# open-usb-can-rev2.net
KiCad netlist of a schematic drawn in EAGLE
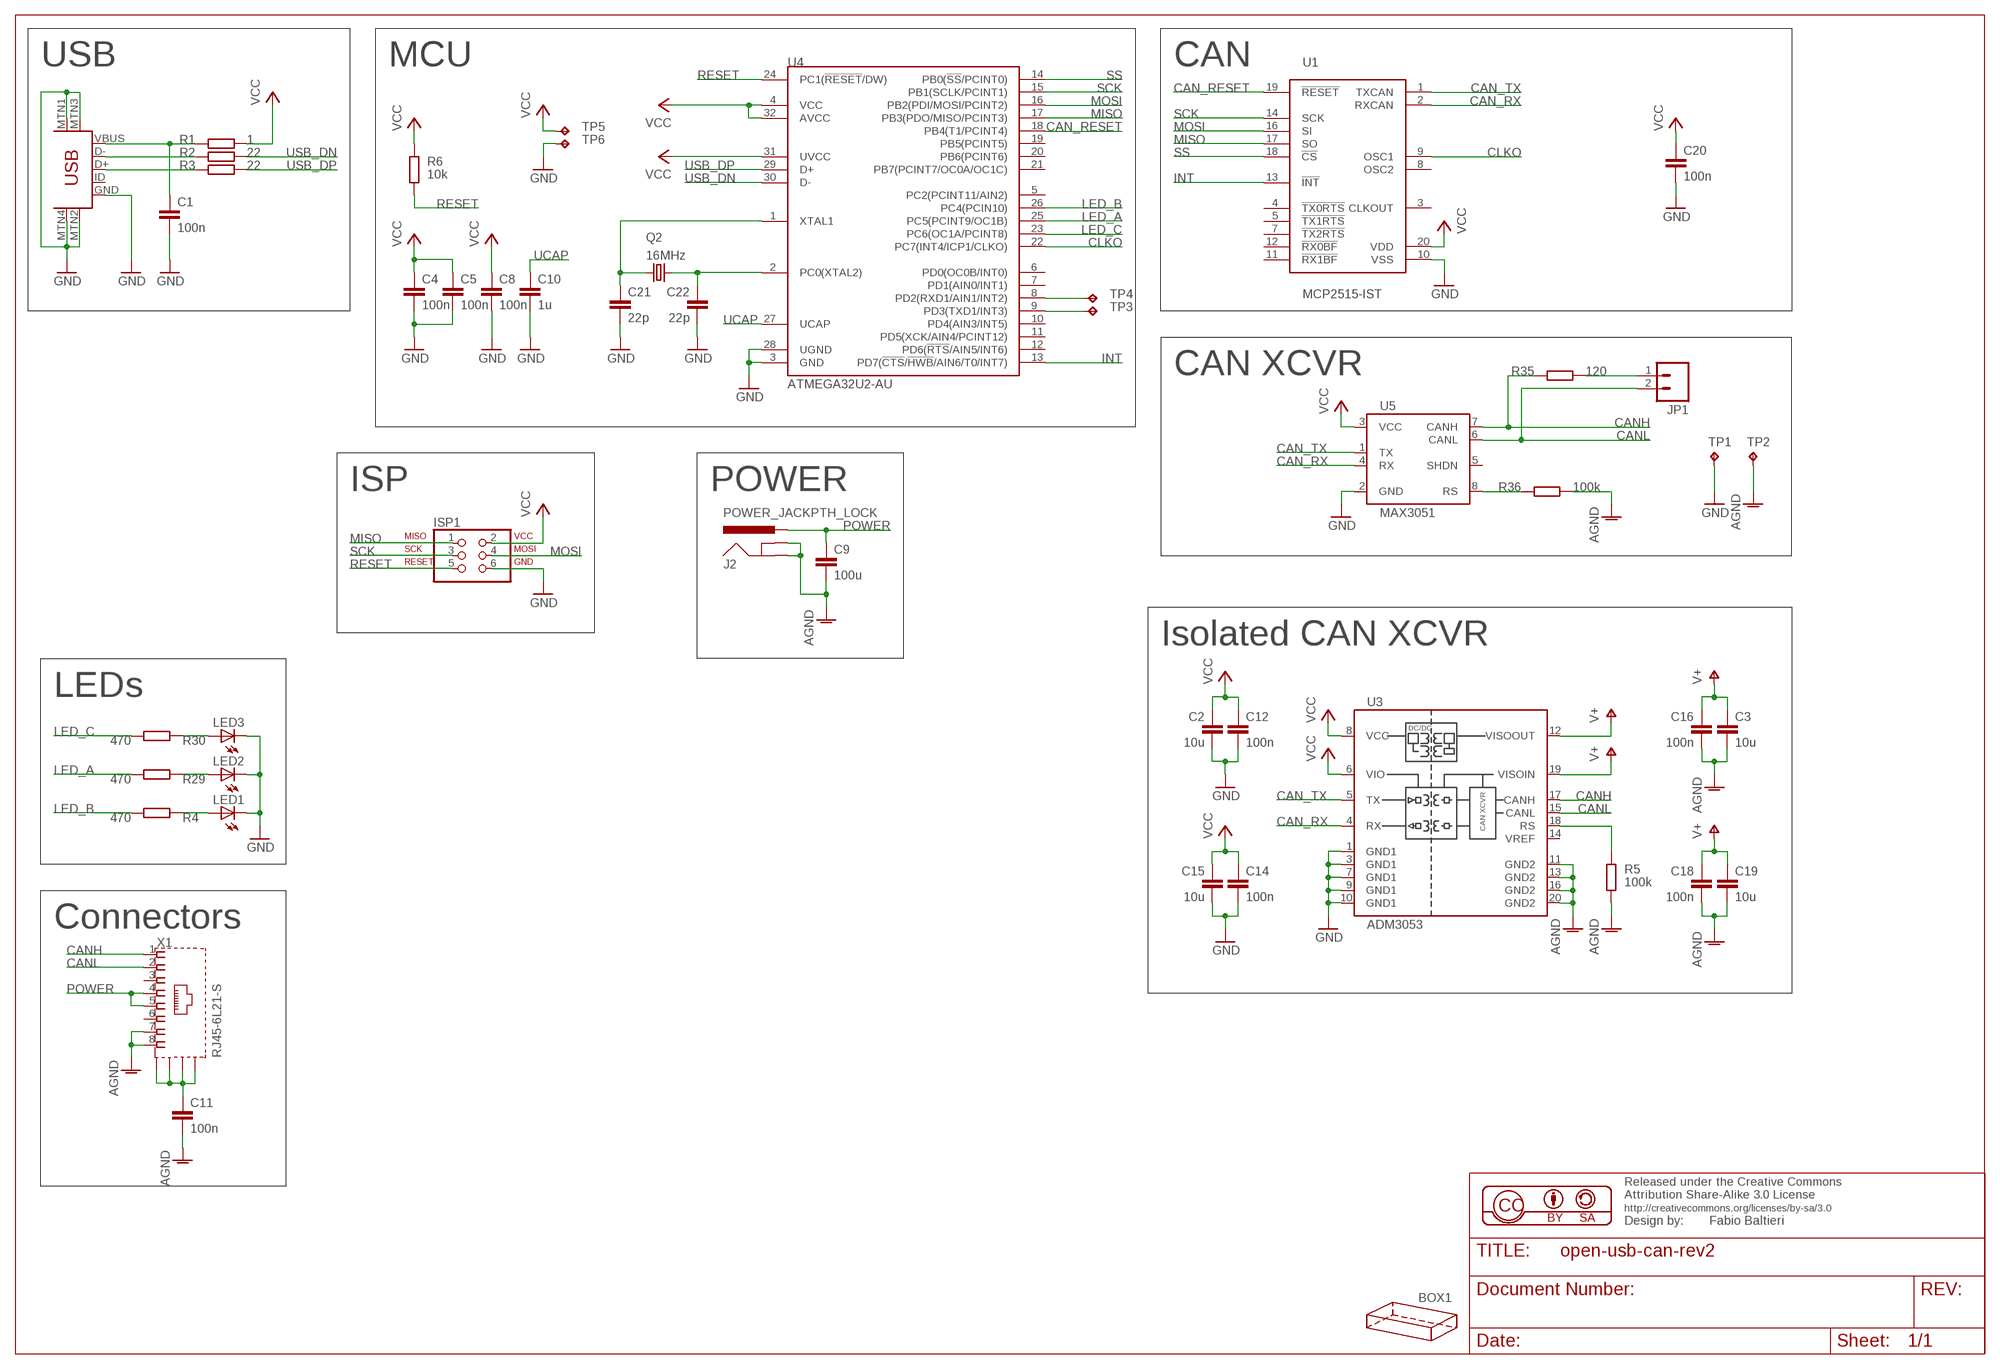
[diagram p0: schematic, sheet 1]

(export (version "E")
  (design (tool "Eeschema 10.0.6"))
  (components
    (comp (ref "BOX1")
      (value "HAMMOND-BOX-R")
      (footprint "eagle-import:1151R")
      (libsource (lib "eagle-import") (part "HAMMOND-BOX-R"))
    )
    (comp (ref "C1")
      (value "100n")
      (footprint "eagle-import:C0805")
      (libsource (lib "eagle-import") (part "C-EUC0805"))
    )
    (comp (ref "C2")
      (value "10u")
      (footprint "eagle-import:C0805")
      (libsource (lib "eagle-import") (part "C-EUC0805"))
    )
    (comp (ref "C3")
      (value "10u")
      (footprint "eagle-import:C0805")
      (libsource (lib "eagle-import") (part "C-EUC0805"))
    )
    (comp (ref "C4")
      (value "100n")
      (footprint "eagle-import:C0805")
      (libsource (lib "eagle-import") (part "C-EUC0805"))
    )
    (comp (ref "C5")
      (value "100n")
      (footprint "eagle-import:C0805")
      (libsource (lib "eagle-import") (part "C-EUC0805"))
    )
    (comp (ref "C8")
      (value "100n")
      (footprint "eagle-import:C0805")
      (libsource (lib "eagle-import") (part "C-EUC0805"))
    )
    (comp (ref "C9")
      (value "100u")
      (footprint "eagle-import:C0805")
      (libsource (lib "eagle-import") (part "C-EUC0805"))
    )
    (comp (ref "C10")
      (value "1u")
      (footprint "eagle-import:C0805")
      (libsource (lib "eagle-import") (part "C-EUC0805"))
    )
    (comp (ref "C11")
      (value "100n")
      (footprint "eagle-import:C0805")
      (libsource (lib "eagle-import") (part "C-EUC0805"))
    )
    (comp (ref "C12")
      (value "100n")
      (footprint "eagle-import:C0805")
      (libsource (lib "eagle-import") (part "C-EUC0805"))
    )
    (comp (ref "C14")
      (value "100n")
      (footprint "eagle-import:C0805")
      (libsource (lib "eagle-import") (part "C-EUC0805"))
    )
    (comp (ref "C15")
      (value "10u")
      (footprint "eagle-import:C0805")
      (libsource (lib "eagle-import") (part "C-EUC0805"))
    )
    (comp (ref "C16")
      (value "100n")
      (footprint "eagle-import:C0805")
      (libsource (lib "eagle-import") (part "C-EUC0805"))
    )
    (comp (ref "C18")
      (value "100n")
      (footprint "eagle-import:C0805")
      (libsource (lib "eagle-import") (part "C-EUC0805"))
    )
    (comp (ref "C19")
      (value "10u")
      (footprint "eagle-import:C0805")
      (libsource (lib "eagle-import") (part "C-EUC0805"))
    )
    (comp (ref "C20")
      (value "100n")
      (footprint "eagle-import:C0805")
      (libsource (lib "eagle-import") (part "C-EUC0805"))
    )
    (comp (ref "C21")
      (value "22p")
      (footprint "eagle-import:C0805")
      (libsource (lib "eagle-import") (part "C-EUC0805"))
    )
    (comp (ref "C22")
      (value "22p")
      (footprint "eagle-import:C0805")
      (libsource (lib "eagle-import") (part "C-EUC0805"))
    )
    (comp (ref "ISP1")
      (value "ISP-AVR910PTH")
      (footprint "eagle-import:2X03")
      (libsource (lib "eagle-import") (part "ISP-AVR910PTH"))
    )
    (comp (ref "J2")
      (value "POWER_JACKPTH_LOCK")
      (footprint "eagle-import:POWER_JACK_PTH_LOCK")
      (libsource (lib "eagle-import") (part "POWER_JACKPTH_LOCK"))
    )
    (comp (ref "JP1")
      (value "M02PTH")
      (footprint "eagle-import:1X02")
      (libsource (lib "eagle-import") (part "M02PTH"))
    )
    (comp (ref "LED1")
      (value "LEDCHIPLED_0805")
      (footprint "eagle-import:CHIPLED_0805")
      (libsource (lib "eagle-import") (part "LEDCHIPLED_0805"))
    )
    (comp (ref "LED2")
      (value "LEDCHIPLED_0805")
      (footprint "eagle-import:CHIPLED_0805")
      (libsource (lib "eagle-import") (part "LEDCHIPLED_0805"))
    )
    (comp (ref "LED3")
      (value "LEDCHIPLED_0805")
      (footprint "eagle-import:CHIPLED_0805")
      (libsource (lib "eagle-import") (part "LEDCHIPLED_0805"))
    )
    (comp (ref "Q2")
      (value "16MHz")
      (footprint "eagle-import:CRYSTAL-SMD-5X3")
      (libsource (lib "eagle-import") (part "CRYSTAL5X3"))
    )
    (comp (ref "R1")
      (value "1")
      (footprint "eagle-import:R0603")
      (libsource (lib "eagle-import") (part "R-EU_R0603"))
    )
    (comp (ref "R2")
      (value "22")
      (footprint "eagle-import:R0603")
      (libsource (lib "eagle-import") (part "R-EU_R0603"))
    )
    (comp (ref "R3")
      (value "22")
      (footprint "eagle-import:R0603")
      (libsource (lib "eagle-import") (part "R-EU_R0603"))
    )
    (comp (ref "R4")
      (value "470")
      (footprint "eagle-import:R0603")
      (libsource (lib "eagle-import") (part "R-EU_R0603"))
    )
    (comp (ref "R5")
      (value "100k")
      (footprint "eagle-import:R0603")
      (libsource (lib "eagle-import") (part "R-EU_R0603"))
    )
    (comp (ref "R6")
      (value "10k")
      (footprint "eagle-import:R0603")
      (libsource (lib "eagle-import") (part "R-EU_R0603"))
    )
    (comp (ref "R29")
      (value "470")
      (footprint "eagle-import:R0603")
      (libsource (lib "eagle-import") (part "R-EU_R0603"))
    )
    (comp (ref "R30")
      (value "470")
      (footprint "eagle-import:R0603")
      (libsource (lib "eagle-import") (part "R-EU_R0603"))
    )
    (comp (ref "R35")
      (value "120")
      (footprint "eagle-import:R0805")
      (libsource (lib "eagle-import") (part "R-EU_R0805"))
    )
    (comp (ref "R36")
      (value "100k")
      (footprint "eagle-import:R0603")
      (libsource (lib "eagle-import") (part "R-EU_R0603"))
    )
    (comp (ref "TP1")
      (value "TPTP16SQ")
      (footprint "eagle-import:TP16SQ")
      (libsource (lib "eagle-import") (part "TPTP16SQ"))
    )
    (comp (ref "TP2")
      (value "TPTP16SQ")
      (footprint "eagle-import:TP16SQ")
      (libsource (lib "eagle-import") (part "TPTP16SQ"))
    )
    (comp (ref "TP3")
      (value "TPTP11R")
      (footprint "eagle-import:TP11R")
      (libsource (lib "eagle-import") (part "TPTP11R"))
    )
    (comp (ref "TP4")
      (value "TPTP11R")
      (footprint "eagle-import:TP11R")
      (libsource (lib "eagle-import") (part "TPTP11R"))
    )
    (comp (ref "TP5")
      (value "TPTP11R")
      (footprint "eagle-import:TP11R")
      (libsource (lib "eagle-import") (part "TPTP11R"))
    )
    (comp (ref "TP6")
      (value "TPTP11R")
      (footprint "eagle-import:TP11R")
      (libsource (lib "eagle-import") (part "TPTP11R"))
    )
    (comp (ref "U$2")
      (value "USB-MINIB-5PIN")
      (footprint "eagle-import:USB-MINIB")
      (libsource (lib "eagle-import") (part "USB-MINIB-5PIN"))
    )
    (comp (ref "U1")
      (value "MCP2515-IST")
      (footprint "eagle-import:TSSOP20")
      (libsource (lib "eagle-import") (part "MCP2515-IST"))
    )
    (comp (ref "U3")
      (value "ADM3053")
      (footprint "eagle-import:SO20W")
      (libsource (lib "eagle-import") (part "ADM3053"))
    )
    (comp (ref "U4")
      (value "ATMEGA32U2-AU")
      (footprint "eagle-import:TQFP32-08")
      (libsource (lib "eagle-import") (part "ATMEGA32U2-AU"))
    )
    (comp (ref "U5")
      (value "MAX3051")
      (footprint "eagle-import:SO08")
      (libsource (lib "eagle-import") (part "MAX3051"))
    )
    (comp (ref "X1")
      (value "RJ45-6L21-S")
      (footprint "eagle-import:RJ45-SHIELD1")
      (libsource (lib "eagle-import") (part "RJ4521-S-6L"))
    )
  )
  (nets
    (net (code "1") (name "/CANH") (class "Default")
      (node (ref "R35") (pin "1") (pinfunction "1_1") (pintype "passive"))
      (node (ref "U3") (pin "17") (pinfunction "CANH_17") (pintype "bidirectional"))
      (node (ref "U5") (pin "7") (pinfunction "CANH_7") (pintype "bidirectional"))
      (node (ref "X1") (pin "1") (pinfunction "1_1") (pintype "passive"))
    )
    (net (code "2") (name "/CANL") (class "Default")
      (node (ref "JP1") (pin "2") (pinfunction "2_2") (pintype "passive"))
      (node (ref "U3") (pin "15") (pinfunction "CANL_15") (pintype "bidirectional"))
      (node (ref "U5") (pin "6") (pinfunction "CANL_6") (pintype "bidirectional"))
      (node (ref "X1") (pin "2") (pinfunction "2_2") (pintype "passive"))
    )
    (net (code "3") (name "/CAN_RESET") (class "Default")
      (node (ref "U1") (pin "19") (pinfunction "~{RESET}_19") (pintype "bidirectional"))
      (node (ref "U4") (pin "18") (pinfunction "PB4(T1/PCINT4)_18") (pintype "bidirectional"))
    )
    (net (code "4") (name "/CAN_RX") (class "Default")
      (node (ref "U1") (pin "2") (pinfunction "RXCAN_2") (pintype "bidirectional"))
      (node (ref "U3") (pin "4") (pinfunction "RX_4") (pintype "bidirectional"))
      (node (ref "U5") (pin "4") (pinfunction "RX_4") (pintype "bidirectional"))
    )
    (net (code "5") (name "/CAN_TX") (class "Default")
      (node (ref "U1") (pin "1") (pinfunction "TXCAN_1") (pintype "bidirectional"))
      (node (ref "U3") (pin "5") (pinfunction "TX_5") (pintype "bidirectional"))
      (node (ref "U5") (pin "1") (pinfunction "TX_1") (pintype "bidirectional"))
    )
    (net (code "6") (name "/CLKO") (class "Default")
      (node (ref "U1") (pin "9") (pinfunction "OSC1_9") (pintype "bidirectional"))
      (node (ref "U4") (pin "22") (pinfunction "PC7(INT4/ICP1/CLKO)_22") (pintype "bidirectional"))
    )
    (net (code "7") (name "/INT") (class "Default")
      (node (ref "U1") (pin "13") (pinfunction "~{INT}_13") (pintype "bidirectional"))
      (node (ref "U4") (pin "13") (pinfunction "PD7(~{CTS}/~{HWB}/AIN6/T0/INT7)_13") (pintype "bidirectional"))
    )
    (net (code "8") (name "/LED_A") (class "Default")
      (node (ref "R29") (pin "2") (pinfunction "2_2") (pintype "passive"))
      (node (ref "U4") (pin "25") (pinfunction "PC5(PCINT9/OC1B)_25") (pintype "bidirectional"))
    )
    (net (code "9") (name "/LED_B") (class "Default")
      (node (ref "R4") (pin "2") (pinfunction "2_2") (pintype "passive"))
      (node (ref "U4") (pin "26") (pinfunction "PC4(PCIN10)_26") (pintype "bidirectional"))
    )
    (net (code "10") (name "/LED_C") (class "Default")
      (node (ref "R30") (pin "2") (pinfunction "2_2") (pintype "passive"))
      (node (ref "U4") (pin "23") (pinfunction "PC6(OC1A/PCINT8)_23") (pintype "bidirectional"))
    )
    (net (code "11") (name "/MISO") (class "Default")
      (node (ref "ISP1") (pin "1") (pinfunction "1_1") (pintype "passive"))
      (node (ref "U1") (pin "17") (pinfunction "SO_17") (pintype "bidirectional"))
      (node (ref "U4") (pin "17") (pinfunction "PB3(PDO/MISO/PCINT3)_17") (pintype "bidirectional"))
    )
    (net (code "12") (name "/MOSI") (class "Default")
      (node (ref "ISP1") (pin "4") (pinfunction "4_4") (pintype "passive"))
      (node (ref "U1") (pin "16") (pinfunction "SI_16") (pintype "bidirectional"))
      (node (ref "U4") (pin "16") (pinfunction "PB2(PDI/MOSI/PCINT2)_16") (pintype "bidirectional"))
    )
    (net (code "13") (name "/POWER") (class "Default")
      (node (ref "C9") (pin "1") (pinfunction "1_1") (pintype "passive"))
      (node (ref "J2") (pin "PWR") (pinfunction "PWR_PWR") (pintype "bidirectional"))
      (node (ref "X1") (pin "4") (pinfunction "4_4") (pintype "passive"))
      (node (ref "X1") (pin "5") (pinfunction "5_5") (pintype "passive"))
    )
    (net (code "14") (name "/RESET") (class "Default")
      (node (ref "ISP1") (pin "5") (pinfunction "5_5") (pintype "passive"))
      (node (ref "R6") (pin "2") (pinfunction "2_2") (pintype "passive"))
      (node (ref "U4") (pin "24") (pinfunction "PC1(~{RESET}/DW)_24") (pintype "bidirectional"))
    )
    (net (code "15") (name "/SCK") (class "Default")
      (node (ref "ISP1") (pin "3") (pinfunction "3_3") (pintype "passive"))
      (node (ref "U1") (pin "14") (pinfunction "SCK_14") (pintype "bidirectional"))
      (node (ref "U4") (pin "15") (pinfunction "PB1(SCLK/PCINT1)_15") (pintype "bidirectional"))
    )
    (net (code "16") (name "/SS") (class "Default")
      (node (ref "U1") (pin "18") (pinfunction "~{CS}_18") (pintype "bidirectional"))
      (node (ref "U4") (pin "14") (pinfunction "PB0(~{SS}/PCINT0)_14") (pintype "bidirectional"))
    )
    (net (code "17") (name "/UCAP") (class "Default")
      (node (ref "C10") (pin "1") (pinfunction "1_1") (pintype "passive"))
      (node (ref "U4") (pin "27") (pinfunction "UCAP_27") (pintype "bidirectional"))
    )
    (net (code "18") (name "/USB_DN") (class "Default")
      (node (ref "R2") (pin "2") (pinfunction "2_2") (pintype "passive"))
      (node (ref "U4") (pin "30") (pinfunction "D-_30") (pintype "bidirectional"))
    )
    (net (code "19") (name "/USB_DP") (class "Default")
      (node (ref "R3") (pin "2") (pinfunction "2_2") (pintype "passive"))
      (node (ref "U4") (pin "29") (pinfunction "D+_29") (pintype "bidirectional"))
    )
    (net (code "20") (name "AGND") (class "Default")
      (node (ref "C11") (pin "2") (pinfunction "2_2") (pintype "passive"))
      (node (ref "C16") (pin "2") (pinfunction "2_2") (pintype "passive"))
      (node (ref "C18") (pin "2") (pinfunction "2_2") (pintype "passive"))
      (node (ref "C19") (pin "2") (pinfunction "2_2") (pintype "passive"))
      (node (ref "C3") (pin "2") (pinfunction "2_2") (pintype "passive"))
      (node (ref "C9") (pin "2") (pinfunction "2_2") (pintype "passive"))
      (node (ref "J2") (pin "GND") (pinfunction "GND_GND") (pintype "bidirectional"))
      (node (ref "J2") (pin "GNDBREAK") (pinfunction "GNDBREAK_GNDBREAK") (pintype "bidirectional"))
      (node (ref "R36") (pin "2") (pinfunction "2_2") (pintype "passive"))
      (node (ref "R5") (pin "2") (pinfunction "2_2") (pintype "passive"))
      (node (ref "TP2") (pin "TP") (pinfunction "TP_TP") (pintype "input"))
      (node (ref "U3") (pin "11") (pinfunction "GND2_11") (pintype "bidirectional"))
      (node (ref "U3") (pin "13") (pinfunction "GND2_13") (pintype "bidirectional"))
      (node (ref "U3") (pin "16") (pinfunction "GND2_16") (pintype "bidirectional"))
      (node (ref "U3") (pin "20") (pinfunction "GND2_20") (pintype "bidirectional"))
      (node (ref "X1") (pin "7") (pinfunction "7_7") (pintype "passive"))
      (node (ref "X1") (pin "8") (pinfunction "8_8") (pintype "passive"))
    )
    (net (code "21") (name "GND") (class "Default")
      (node (ref "C1") (pin "2") (pinfunction "2_2") (pintype "passive"))
      (node (ref "C10") (pin "2") (pinfunction "2_2") (pintype "passive"))
      (node (ref "C12") (pin "2") (pinfunction "2_2") (pintype "passive"))
      (node (ref "C14") (pin "2") (pinfunction "2_2") (pintype "passive"))
      (node (ref "C15") (pin "2") (pinfunction "2_2") (pintype "passive"))
      (node (ref "C2") (pin "2") (pinfunction "2_2") (pintype "passive"))
      (node (ref "C20") (pin "2") (pinfunction "2_2") (pintype "passive"))
      (node (ref "C21") (pin "2") (pinfunction "2_2") (pintype "passive"))
      (node (ref "C22") (pin "2") (pinfunction "2_2") (pintype "passive"))
      (node (ref "C4") (pin "2") (pinfunction "2_2") (pintype "passive"))
      (node (ref "C5") (pin "2") (pinfunction "2_2") (pintype "passive"))
      (node (ref "C8") (pin "2") (pinfunction "2_2") (pintype "passive"))
      (node (ref "ISP1") (pin "6") (pinfunction "6_6") (pintype "passive"))
      (node (ref "LED1") (pin "C") (pinfunction "C_C") (pintype "passive"))
      (node (ref "LED2") (pin "C") (pinfunction "C_C") (pintype "passive"))
      (node (ref "LED3") (pin "C") (pinfunction "C_C") (pintype "passive"))
      (node (ref "TP1") (pin "TP") (pinfunction "TP_TP") (pintype "input"))
      (node (ref "TP6") (pin "TP") (pinfunction "TP_TP") (pintype "input"))
      (node (ref "U$2") (pin "GND") (pinfunction "GND_GND") (pintype "bidirectional"))
      (node (ref "U$2") (pin "MTN1") (pinfunction "MTN2_MTN1") (pintype "bidirectional"))
      (node (ref "U$2") (pin "MTN2") (pinfunction "MTN3_MTN2") (pintype "bidirectional"))
      (node (ref "U$2") (pin "MTN3") (pinfunction "MTN1_MTN3") (pintype "bidirectional"))
      (node (ref "U$2") (pin "MTN4") (pinfunction "MTN4_MTN4") (pintype "bidirectional"))
      (node (ref "U1") (pin "10") (pinfunction "VSS_10") (pintype "power_in"))
      (node (ref "U3") (pin "1") (pinfunction "GND1_1") (pintype "bidirectional"))
      (node (ref "U3") (pin "10") (pinfunction "GND1_10") (pintype "bidirectional"))
      (node (ref "U3") (pin "3") (pinfunction "GND1_3") (pintype "bidirectional"))
      (node (ref "U3") (pin "7") (pinfunction "GND1_7") (pintype "bidirectional"))
      (node (ref "U3") (pin "9") (pinfunction "GND1_9") (pintype "bidirectional"))
      (node (ref "U4") (pin "28") (pinfunction "UGND_28") (pintype "bidirectional"))
      (node (ref "U4") (pin "3") (pinfunction "GND_3") (pintype "bidirectional"))
      (node (ref "U5") (pin "2") (pinfunction "GND_2") (pintype "bidirectional"))
    )
    (net (code "22") (name "Net-(C1-Pad1)") (class "Default")
      (node (ref "C1") (pin "1") (pinfunction "1_1") (pintype "passive"))
      (node (ref "R1") (pin "1") (pinfunction "1_1") (pintype "passive"))
      (node (ref "U$2") (pin "VBUS") (pinfunction "VBUS_VBUS") (pintype "bidirectional"))
    )
    (net (code "23") (name "Net-(C11-Pad1)") (class "Default")
      (node (ref "C11") (pin "1") (pinfunction "1_1") (pintype "passive"))
      (node (ref "X1") (pin "S1") (pinfunction "S_S1") (pintype "passive"))
      (node (ref "X1") (pin "S2") (pinfunction "S_S2") (pintype "passive"))
      (node (ref "X1") (pin "S3") (pinfunction "S_S3") (pintype "passive"))
      (node (ref "X1") (pin "S4") (pinfunction "S_S4") (pintype "passive"))
    )
    (net (code "24") (name "Net-(JP1-Pad1)") (class "Default")
      (node (ref "JP1") (pin "1") (pinfunction "1_1") (pintype "passive"))
      (node (ref "R35") (pin "2") (pinfunction "2_2") (pintype "passive"))
    )
    (net (code "25") (name "Net-(LED1-PadA)") (class "Default")
      (node (ref "LED1") (pin "A") (pinfunction "A_A") (pintype "passive"))
      (node (ref "R4") (pin "1") (pinfunction "1_1") (pintype "passive"))
    )
    (net (code "26") (name "Net-(LED2-PadA)") (class "Default")
      (node (ref "LED2") (pin "A") (pinfunction "A_A") (pintype "passive"))
      (node (ref "R29") (pin "1") (pinfunction "1_1") (pintype "passive"))
    )
    (net (code "27") (name "Net-(LED3-PadA)") (class "Default")
      (node (ref "LED3") (pin "A") (pinfunction "A_A") (pintype "passive"))
      (node (ref "R30") (pin "1") (pinfunction "1_1") (pintype "passive"))
    )
    (net (code "28") (name "Net-(Q2-2)") (class "Default")
      (node (ref "C22") (pin "1") (pinfunction "1_1") (pintype "passive"))
      (node (ref "Q2") (pin "3") (pinfunction "2_3") (pintype "passive"))
      (node (ref "U4") (pin "2") (pinfunction "PC0(XTAL2)_2") (pintype "bidirectional"))
    )
    (net (code "29") (name "Net-(R2-Pad1)") (class "Default")
      (node (ref "R2") (pin "1") (pinfunction "1_1") (pintype "passive"))
      (node (ref "U$2") (pin "D-") (pinfunction "D-_D-") (pintype "bidirectional"))
    )
    (net (code "30") (name "Net-(R3-Pad1)") (class "Default")
      (node (ref "R3") (pin "1") (pinfunction "1_1") (pintype "passive"))
      (node (ref "U$2") (pin "D+") (pinfunction "D+_D+") (pintype "bidirectional"))
    )
    (net (code "31") (name "Net-(U3-RS)") (class "Default")
      (node (ref "R5") (pin "1") (pinfunction "1_1") (pintype "passive"))
      (node (ref "U3") (pin "18") (pinfunction "RS_18") (pintype "bidirectional"))
    )
    (net (code "32") (name "Net-(U4-PD2(RXD1{slash}AIN1{slash}INT2))") (class "Default")
      (node (ref "TP4") (pin "TP") (pinfunction "TP_TP") (pintype "input"))
      (node (ref "U4") (pin "8") (pinfunction "PD2(RXD1/AIN1/INT2)_8") (pintype "bidirectional"))
    )
    (net (code "33") (name "Net-(U4-PD3(TXD1{slash}INT3))") (class "Default")
      (node (ref "TP3") (pin "TP") (pinfunction "TP_TP") (pintype "input"))
      (node (ref "U4") (pin "9") (pinfunction "PD3(TXD1/INT3)_9") (pintype "bidirectional"))
    )
    (net (code "34") (name "Net-(U4-XTAL1)") (class "Default")
      (node (ref "C21") (pin "1") (pinfunction "1_1") (pintype "passive"))
      (node (ref "Q2") (pin "1") (pinfunction "1_1") (pintype "passive"))
      (node (ref "U4") (pin "1") (pinfunction "XTAL1_1") (pintype "bidirectional"))
    )
    (net (code "35") (name "Net-(U5-RS)") (class "Default")
      (node (ref "R36") (pin "1") (pinfunction "1_1") (pintype "passive"))
      (node (ref "U5") (pin "8") (pinfunction "RS_8") (pintype "bidirectional"))
    )
    (net (code "36") (name "V+") (class "Default")
      (node (ref "C16") (pin "1") (pinfunction "1_1") (pintype "passive"))
      (node (ref "C18") (pin "1") (pinfunction "1_1") (pintype "passive"))
      (node (ref "C19") (pin "1") (pinfunction "1_1") (pintype "passive"))
      (node (ref "C3") (pin "1") (pinfunction "1_1") (pintype "passive"))
      (node (ref "U3") (pin "12") (pinfunction "VISOOUT_12") (pintype "bidirectional"))
      (node (ref "U3") (pin "19") (pinfunction "VISOIN_19") (pintype "bidirectional"))
    )
    (net (code "37") (name "VCC") (class "Default")
      (node (ref "C12") (pin "1") (pinfunction "1_1") (pintype "passive"))
      (node (ref "C14") (pin "1") (pinfunction "1_1") (pintype "passive"))
      (node (ref "C15") (pin "1") (pinfunction "1_1") (pintype "passive"))
      (node (ref "C2") (pin "1") (pinfunction "1_1") (pintype "passive"))
      (node (ref "C20") (pin "1") (pinfunction "1_1") (pintype "passive"))
      (node (ref "C4") (pin "1") (pinfunction "1_1") (pintype "passive"))
      (node (ref "C5") (pin "1") (pinfunction "1_1") (pintype "passive"))
      (node (ref "C8") (pin "1") (pinfunction "1_1") (pintype "passive"))
      (node (ref "ISP1") (pin "2") (pinfunction "2_2") (pintype "passive"))
      (node (ref "R1") (pin "2") (pinfunction "2_2") (pintype "passive"))
      (node (ref "R6") (pin "1") (pinfunction "1_1") (pintype "passive"))
      (node (ref "TP5") (pin "TP") (pinfunction "TP_TP") (pintype "input"))
      (node (ref "U1") (pin "20") (pinfunction "VDD_20") (pintype "power_in"))
      (node (ref "U3") (pin "6") (pinfunction "VIO_6") (pintype "bidirectional"))
      (node (ref "U3") (pin "8") (pinfunction "VCC_8") (pintype "bidirectional"))
      (node (ref "U4") (pin "31") (pinfunction "UVCC_31") (pintype "bidirectional"))
      (node (ref "U4") (pin "32") (pinfunction "AVCC_32") (pintype "bidirectional"))
      (node (ref "U4") (pin "4") (pinfunction "VCC_4") (pintype "bidirectional"))
      (node (ref "U5") (pin "3") (pinfunction "VCC_3") (pintype "bidirectional"))
    )
    (net (code "38") (name "unconnected-(U$2-PadID)") (class "Default")
      (node (ref "U$2") (pin "ID") (pinfunction "ID_ID") (pintype "bidirectional"))
    )
    (net (code "39") (name "unconnected-(U1-CLKOUT-Pad3)") (class "Default")
      (node (ref "U1") (pin "3") (pinfunction "CLKOUT_3") (pintype "bidirectional"))
    )
    (net (code "40") (name "unconnected-(U1-OSC2-Pad8)") (class "Default")
      (node (ref "U1") (pin "8") (pinfunction "OSC2_8") (pintype "bidirectional"))
    )
    (net (code "41") (name "unconnected-(U1-~{RX0BF}-Pad12)") (class "Default")
      (node (ref "U1") (pin "12") (pinfunction "~{RX0BF}_12") (pintype "bidirectional"))
    )
    (net (code "42") (name "unconnected-(U1-~{RX1BF}-Pad11)") (class "Default")
      (node (ref "U1") (pin "11") (pinfunction "~{RX1BF}_11") (pintype "bidirectional"))
    )
    (net (code "43") (name "unconnected-(U1-~{TX0RTS}-Pad4)") (class "Default")
      (node (ref "U1") (pin "4") (pinfunction "~{TX0RTS}_4") (pintype "bidirectional"))
    )
    (net (code "44") (name "unconnected-(U1-~{TX1RTS}-Pad5)") (class "Default")
      (node (ref "U1") (pin "5") (pinfunction "~{TX1RTS}_5") (pintype "bidirectional"))
    )
    (net (code "45") (name "unconnected-(U1-~{TX2RTS}-Pad7)") (class "Default")
      (node (ref "U1") (pin "7") (pinfunction "~{TX2RTS}_7") (pintype "bidirectional"))
    )
    (net (code "46") (name "unconnected-(U3-NC-Pad2)") (class "Default")
      (node (ref "U3") (pin "2") (pinfunction "NC_2") (pintype "bidirectional"))
    )
    (net (code "47") (name "unconnected-(U3-VREF-Pad14)") (class "Default")
      (node (ref "U3") (pin "14") (pinfunction "VREF_14") (pintype "bidirectional"))
    )
    (net (code "48") (name "unconnected-(U4-PB5(PCINT5)-Pad19)") (class "Default")
      (node (ref "U4") (pin "19") (pinfunction "PB5(PCINT5)_19") (pintype "bidirectional"))
    )
    (net (code "49") (name "unconnected-(U4-PB6(PCINT6)-Pad20)") (class "Default")
      (node (ref "U4") (pin "20") (pinfunction "PB6(PCINT6)_20") (pintype "bidirectional"))
    )
    (net (code "50") (name "unconnected-(U4-PB7(PCINT7{slash}OC0A{slash}OC1C)-Pad21)") (class "Default")
      (node (ref "U4") (pin "21") (pinfunction "PB7(PCINT7/OC0A/OC1C)_21") (pintype "bidirectional"))
    )
    (net (code "51") (name "unconnected-(U4-PC2(PCINT11{slash}AIN2)-Pad5)") (class "Default")
      (node (ref "U4") (pin "5") (pinfunction "PC2(PCINT11/AIN2)_5") (pintype "bidirectional"))
    )
    (net (code "52") (name "unconnected-(U4-PD0(OC0B{slash}INT0)-Pad6)") (class "Default")
      (node (ref "U4") (pin "6") (pinfunction "PD0(OC0B/INT0)_6") (pintype "bidirectional"))
    )
    (net (code "53") (name "unconnected-(U4-PD1(AIN0{slash}INT1)-Pad7)") (class "Default")
      (node (ref "U4") (pin "7") (pinfunction "PD1(AIN0/INT1)_7") (pintype "bidirectional"))
    )
    (net (code "54") (name "unconnected-(U4-PD4(AIN3{slash}INT5)-Pad10)") (class "Default")
      (node (ref "U4") (pin "10") (pinfunction "PD4(AIN3/INT5)_10") (pintype "bidirectional"))
    )
    (net (code "55") (name "unconnected-(U4-PD5(XCK{slash}AIN4{slash}PCINT12)-Pad11)") (class "Default")
      (node (ref "U4") (pin "11") (pinfunction "PD5(XCK/AIN4/PCINT12)_11") (pintype "bidirectional"))
    )
    (net (code "56") (name "unconnected-(U4-PD6(~{RTS}{slash}AIN5{slash}INT6)-Pad12)") (class "Default")
      (node (ref "U4") (pin "12") (pinfunction "PD6(~{RTS}/AIN5/INT6)_12") (pintype "bidirectional"))
    )
    (net (code "57") (name "unconnected-(U5-SHDN-Pad5)") (class "Default")
      (node (ref "U5") (pin "5") (pinfunction "SHDN_5") (pintype "bidirectional"))
    )
    (net (code "58") (name "unconnected-(X1-Pad3)") (class "Default")
      (node (ref "X1") (pin "3") (pinfunction "3_3") (pintype "passive"))
    )
    (net (code "59") (name "unconnected-(X1-Pad6)") (class "Default")
      (node (ref "X1") (pin "6") (pinfunction "6_6") (pintype "passive"))
    )
  )
)
